# parasit.net
KiCad netlist of a schematic drawn in EAGLE
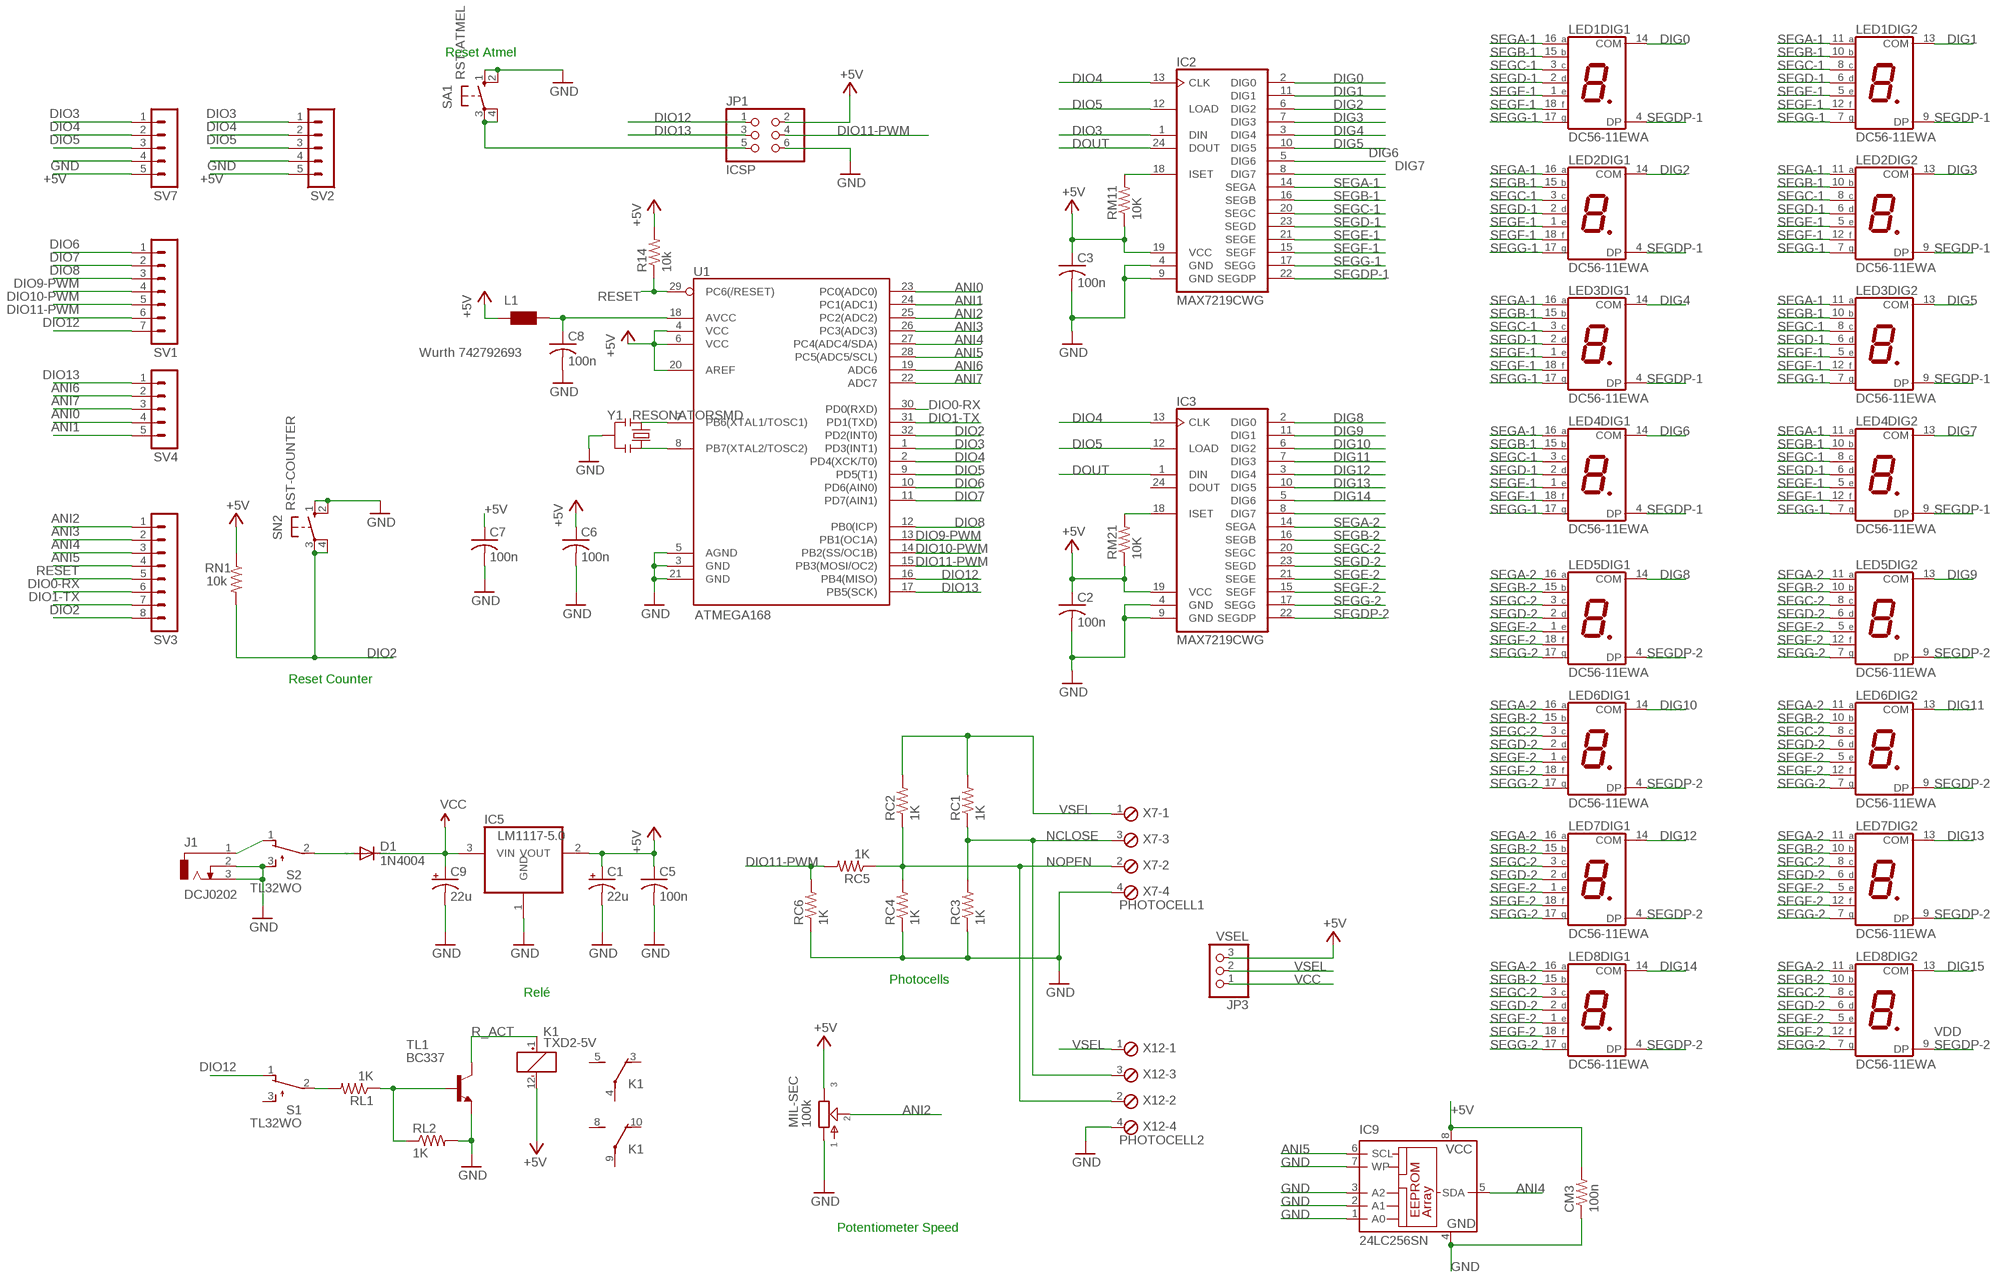
[diagram p0: schematic, sheet 1]

(export (version "E")
  (design (tool "Eeschema 10.0.6"))
  (components
    (comp (ref "C1")
      (value "22u")
      (footprint "eagle-import:PANASONIC_C")
      (libsource (lib "eagle-import") (part "CPOL-USC"))
    )
    (comp (ref "C2")
      (value "100n")
      (footprint "eagle-import:C0603")
      (libsource (lib "eagle-import") (part "C-USC0603"))
    )
    (comp (ref "C3")
      (value "100n")
      (footprint "eagle-import:C0603")
      (libsource (lib "eagle-import") (part "C-USC0603"))
    )
    (comp (ref "C5")
      (value "100n")
      (footprint "eagle-import:C0603")
      (libsource (lib "eagle-import") (part "C-USC0603"))
    )
    (comp (ref "C6")
      (value "100n")
      (footprint "eagle-import:C0603")
      (libsource (lib "eagle-import") (part "C-USC0603"))
    )
    (comp (ref "C7")
      (value "100n")
      (footprint "eagle-import:C0603")
      (libsource (lib "eagle-import") (part "C-USC0603"))
    )
    (comp (ref "C8")
      (value "100n")
      (footprint "eagle-import:C0603")
      (libsource (lib "eagle-import") (part "C-USC0603"))
    )
    (comp (ref "C9")
      (value "22u")
      (footprint "eagle-import:PANASONIC_C")
      (libsource (lib "eagle-import") (part "CPOL-USC"))
    )
    (comp (ref "CM3")
      (value "100n")
      (footprint "eagle-import:R0603")
      (libsource (lib "eagle-import") (part "resistor_R-US_R0603"))
    )
    (comp (ref "D1")
      (value "1N4004")
      (footprint "eagle-import:DO41-10")
      (libsource (lib "eagle-import") (part "1N4004"))
    )
    (comp (ref "IC2")
      (value "MAX7219CWG")
      (footprint "eagle-import:SO24W")
      (libsource (lib "eagle-import") (part "MAX7219WGC"))
    )
    (comp (ref "IC3")
      (value "MAX7219CWG")
      (footprint "eagle-import:SO24W")
      (libsource (lib "eagle-import") (part "MAX7219WGC"))
    )
    (comp (ref "IC5")
      (value "LM1117-5.0")
      (footprint "eagle-import:SOT223")
      (libsource (lib "eagle-import") (part "REG1117"))
    )
    (comp (ref "IC9")
      (value "24LC256SN")
      (footprint "eagle-import:SO-08")
      (fields (field (name "MF") "MICROCHIP") (field (name "MPN") "24LC256-I/SN"))
      (libsource (lib "eagle-import") (part "24SNLC256"))
    )
    (comp (ref "J1")
      (value "DCJ0202")
      (footprint "eagle-import:DCJ0202")
      (libsource (lib "eagle-import") (part "DCJ0202"))
    )
    (comp (ref "JP1")
      (value "ICSP")
      (footprint "eagle-import:2X03")
      (libsource (lib "eagle-import") (part "PINHD-2X3"))
    )
    (comp (ref "JP3")
      (value "VSEL")
      (footprint "eagle-import:1X03")
      (libsource (lib "eagle-import") (part "PINHD-1X3"))
    )
    (comp (ref "K1")
      (value "TXD2-5V")
      (footprint "eagle-import:TXD2")
      (libsource (lib "eagle-import") (part "TX?-D25V"))
    )
    (comp (ref "L1")
      (value "WE-CBF_0603")
      (footprint "eagle-import:0603")
      (libsource (lib "eagle-import") (part "WE-CBF_0603"))
    )
    (comp (ref "LED1")
      (value "DC56-11EWA")
      (footprint "eagle-import:DA56")
      (libsource (lib "eagle-import") (part "DC56-11EWA"))
    )
    (comp (ref "LED2")
      (value "DC56-11EWA")
      (footprint "eagle-import:DA56")
      (libsource (lib "eagle-import") (part "DC56-11EWA"))
    )
    (comp (ref "LED3")
      (value "DC56-11EWA")
      (footprint "eagle-import:DA56")
      (libsource (lib "eagle-import") (part "DC56-11EWA"))
    )
    (comp (ref "LED4")
      (value "DC56-11EWA")
      (footprint "eagle-import:DA56")
      (libsource (lib "eagle-import") (part "DC56-11EWA"))
    )
    (comp (ref "LED5")
      (value "DC56-11EWA")
      (footprint "eagle-import:DA56")
      (libsource (lib "eagle-import") (part "DC56-11EWA"))
    )
    (comp (ref "LED6")
      (value "DC56-11EWA")
      (footprint "eagle-import:DA56")
      (libsource (lib "eagle-import") (part "DC56-11EWA"))
    )
    (comp (ref "LED7")
      (value "DC56-11EWA")
      (footprint "eagle-import:DA56")
      (libsource (lib "eagle-import") (part "DC56-11EWA"))
    )
    (comp (ref "LED8")
      (value "DC56-11EWA")
      (footprint "eagle-import:DA56")
      (libsource (lib "eagle-import") (part "DC56-11EWA"))
    )
    (comp (ref "MIL-SEC")
      (value "100k")
      (footprint "eagle-import:16MM-PCB-BRACKETS@1")
      (libsource (lib "eagle-import") (part "16MM-PCB-BRACKETS"))
    )
    (comp (ref "R14")
      (value "10k")
      (footprint "eagle-import:R0603")
      (libsource (lib "eagle-import") (part "R-US_R0603"))
    )
    (comp (ref "RC1")
      (value "1K")
      (footprint "eagle-import:R0603")
      (libsource (lib "eagle-import") (part "R-US_R0603"))
    )
    (comp (ref "RC2")
      (value "1K")
      (footprint "eagle-import:R0603")
      (libsource (lib "eagle-import") (part "R-US_R0603"))
    )
    (comp (ref "RC3")
      (value "1K")
      (footprint "eagle-import:R0603")
      (libsource (lib "eagle-import") (part "R-US_R0603"))
    )
    (comp (ref "RC4")
      (value "1K")
      (footprint "eagle-import:R0603")
      (libsource (lib "eagle-import") (part "R-US_R0603"))
    )
    (comp (ref "RC5")
      (value "1K")
      (footprint "eagle-import:R0603")
      (libsource (lib "eagle-import") (part "R-US_R0603"))
    )
    (comp (ref "RC6")
      (value "1K")
      (footprint "eagle-import:R0603")
      (libsource (lib "eagle-import") (part "resistor_R-US_R0603"))
    )
    (comp (ref "RL1")
      (value "1K")
      (footprint "eagle-import:R0603")
      (libsource (lib "eagle-import") (part "resistor_R-US_R0603"))
    )
    (comp (ref "RL2")
      (value "1K")
      (footprint "eagle-import:R0603")
      (libsource (lib "eagle-import") (part "resistor_R-US_R0603"))
    )
    (comp (ref "RM11")
      (value "10K")
      (footprint "eagle-import:R0603")
      (libsource (lib "eagle-import") (part "R-US_R0603"))
    )
    (comp (ref "RM21")
      (value "10K")
      (footprint "eagle-import:R0603")
      (libsource (lib "eagle-import") (part "R-US_R0603"))
    )
    (comp (ref "RN1")
      (value "10k")
      (footprint "eagle-import:R0603")
      (libsource (lib "eagle-import") (part "R-US_R0603"))
    )
    (comp (ref "S1")
      (value "TL32WO")
      (footprint "eagle-import:TL3XWO")
      (libsource (lib "eagle-import") (part "TL32WO"))
    )
    (comp (ref "S2")
      (value "TL32WO")
      (footprint "eagle-import:TL3XWO")
      (libsource (lib "eagle-import") (part "TL32WO"))
    )
    (comp (ref "SA1")
      (value "RST-ATMEL")
      (footprint "eagle-import:B3F-10XX")
      (fields (field (name "MPN") "B3F-1000"))
      (libsource (lib "eagle-import") (part "10-XX"))
    )
    (comp (ref "SN2")
      (value "RST-COUNTER")
      (footprint "eagle-import:B3F-10XX")
      (fields (field (name "MPN") "B3F-1000"))
      (libsource (lib "eagle-import") (part "10-XX"))
    )
    (comp (ref "SV1")
      (value "MA07-1")
      (footprint "eagle-import:MA07-1")
      (libsource (lib "eagle-import") (part "MA07-1"))
    )
    (comp (ref "SV2")
      (value "MA05-1")
      (footprint "eagle-import:MA05-1")
      (libsource (lib "eagle-import") (part "MA05-1"))
    )
    (comp (ref "SV3")
      (value "MA08-1")
      (footprint "eagle-import:MA08-1")
      (libsource (lib "eagle-import") (part "MA08-1"))
    )
    (comp (ref "SV4")
      (value "MA05-1")
      (footprint "eagle-import:MA05-1")
      (libsource (lib "eagle-import") (part "MA05-1"))
    )
    (comp (ref "SV7")
      (value "MA05-1")
      (footprint "eagle-import:MA05-1")
      (libsource (lib "eagle-import") (part "MA05-1"))
    )
    (comp (ref "TL1")
      (value "BC337")
      (footprint "eagle-import:TO92")
      (libsource (lib "eagle-import") (part "BC337"))
    )
    (comp (ref "U1")
      (value "ATMEGA168")
      (footprint "eagle-import:TQFP32-08")
      (libsource (lib "eagle-import") (part "ATMEGA168"))
    )
    (comp (ref "X7")
      (value "PHOTOCELL1")
      (footprint "eagle-import:4POL254")
      (libsource (lib "eagle-import") (part "MPT4"))
    )
    (comp (ref "X12")
      (value "PHOTOCELL2")
      (footprint "eagle-import:4POL254")
      (libsource (lib "eagle-import") (part "MPT4"))
    )
    (comp (ref "Y1")
      (value "RESONATORSMD")
      (footprint "eagle-import:RESONATOR-SMD")
      (libsource (lib "eagle-import") (part "RESONATORSMD"))
    )
  )
  (nets
    (net (code "1") (name "+5V") (class "Default")
      (node (ref "C1") (pin "+") (pinfunction "+_+") (pintype "passive"))
      (node (ref "C2") (pin "1") (pinfunction "1_1") (pintype "passive"))
      (node (ref "C3") (pin "1") (pinfunction "1_1") (pintype "passive"))
      (node (ref "C5") (pin "1") (pinfunction "1_1") (pintype "passive"))
      (node (ref "C6") (pin "1") (pinfunction "1_1") (pintype "passive"))
      (node (ref "C7") (pin "1") (pinfunction "1_1") (pintype "passive"))
      (node (ref "CM3") (pin "2") (pinfunction "2_2") (pintype "passive"))
      (node (ref "IC2") (pin "19") (pinfunction "VCC_19") (pintype "power_in"))
      (node (ref "IC3") (pin "19") (pinfunction "VCC_19") (pintype "power_in"))
      (node (ref "IC5") (pin "2") (pinfunction "VOUT_2") (pintype "output"))
      (node (ref "IC9") (pin "8") (pinfunction "VCC_8") (pintype "power_in"))
      (node (ref "JP1") (pin "2") (pinfunction "2_2") (pintype "passive"))
      (node (ref "JP3") (pin "3") (pinfunction "3_3") (pintype "passive"))
      (node (ref "K1") (pin "12") (pinfunction "-_12") (pintype "passive"))
      (node (ref "L1") (pin "1") (pinfunction "1_1") (pintype "passive"))
      (node (ref "MIL-SEC") (pin "3") (pinfunction "3_3") (pintype "passive"))
      (node (ref "R14") (pin "2") (pinfunction "2_2") (pintype "passive"))
      (node (ref "RM11") (pin "1") (pinfunction "1_1") (pintype "passive"))
      (node (ref "RM21") (pin "1") (pinfunction "1_1") (pintype "passive"))
      (node (ref "RN1") (pin "1") (pinfunction "1_1") (pintype "passive"))
      (node (ref "SV2") (pin "5") (pinfunction "5_5") (pintype "passive"))
      (node (ref "SV7") (pin "5") (pinfunction "5_5") (pintype "passive"))
      (node (ref "U1") (pin "20") (pinfunction "AREF_20") (pintype "bidirectional"))
      (node (ref "U1") (pin "4") (pinfunction "VCC_4") (pintype "bidirectional"))
      (node (ref "U1") (pin "6") (pinfunction "VCC_6") (pintype "bidirectional"))
    )
    (net (code "2") (name "/ANI0") (class "Default")
      (node (ref "SV4") (pin "4") (pinfunction "4_4") (pintype "passive"))
      (node (ref "U1") (pin "23") (pinfunction "PC0(ADC0)_23") (pintype "bidirectional"))
    )
    (net (code "3") (name "/ANI1") (class "Default")
      (node (ref "SV4") (pin "5") (pinfunction "5_5") (pintype "passive"))
      (node (ref "U1") (pin "24") (pinfunction "PC1(ADC1)_24") (pintype "bidirectional"))
    )
    (net (code "4") (name "/ANI2") (class "Default")
      (node (ref "MIL-SEC") (pin "2") (pinfunction "2_2") (pintype "passive"))
      (node (ref "SV3") (pin "1") (pinfunction "1_1") (pintype "passive"))
      (node (ref "U1") (pin "25") (pinfunction "PC2(ADC2)_25") (pintype "bidirectional"))
    )
    (net (code "5") (name "/ANI3") (class "Default")
      (node (ref "SV3") (pin "2") (pinfunction "2_2") (pintype "passive"))
      (node (ref "U1") (pin "26") (pinfunction "PC3(ADC3)_26") (pintype "bidirectional"))
    )
    (net (code "6") (name "/ANI4") (class "Default")
      (node (ref "IC9") (pin "5") (pinfunction "SDA_5") (pintype "bidirectional"))
      (node (ref "SV3") (pin "3") (pinfunction "3_3") (pintype "passive"))
      (node (ref "U1") (pin "27") (pinfunction "PC4(ADC4/SDA)_27") (pintype "bidirectional"))
    )
    (net (code "7") (name "/ANI5") (class "Default")
      (node (ref "IC9") (pin "6") (pinfunction "SCL_6") (pintype "input"))
      (node (ref "SV3") (pin "4") (pinfunction "4_4") (pintype "passive"))
      (node (ref "U1") (pin "28") (pinfunction "PC5(ADC5/SCL)_28") (pintype "bidirectional"))
    )
    (net (code "8") (name "/ANI6") (class "Default")
      (node (ref "SV4") (pin "2") (pinfunction "2_2") (pintype "passive"))
      (node (ref "U1") (pin "19") (pinfunction "ADC6_19") (pintype "bidirectional"))
    )
    (net (code "9") (name "/ANI7") (class "Default")
      (node (ref "SV4") (pin "3") (pinfunction "3_3") (pintype "passive"))
      (node (ref "U1") (pin "22") (pinfunction "ADC7_22") (pintype "bidirectional"))
    )
    (net (code "10") (name "/DIG0") (class "Default")
      (node (ref "IC2") (pin "2") (pinfunction "DIG0_2") (pintype "output"))
      (node (ref "LED1") (pin "14") (pinfunction "COM_14") (pintype "passive"))
    )
    (net (code "11") (name "/DIG1") (class "Default")
      (node (ref "IC2") (pin "11") (pinfunction "DIG1_11") (pintype "output"))
      (node (ref "LED1") (pin "13") (pinfunction "COM_13") (pintype "passive"))
    )
    (net (code "12") (name "/DIG2") (class "Default")
      (node (ref "IC2") (pin "6") (pinfunction "DIG2_6") (pintype "output"))
      (node (ref "LED2") (pin "14") (pinfunction "COM_14") (pintype "passive"))
    )
    (net (code "13") (name "/DIG3") (class "Default")
      (node (ref "IC2") (pin "7") (pinfunction "DIG3_7") (pintype "output"))
      (node (ref "LED2") (pin "13") (pinfunction "COM_13") (pintype "passive"))
    )
    (net (code "14") (name "/DIG4") (class "Default")
      (node (ref "IC2") (pin "3") (pinfunction "DIG4_3") (pintype "output"))
      (node (ref "LED3") (pin "14") (pinfunction "COM_14") (pintype "passive"))
    )
    (net (code "15") (name "/DIG5") (class "Default")
      (node (ref "IC2") (pin "10") (pinfunction "DIG5_10") (pintype "output"))
      (node (ref "LED3") (pin "13") (pinfunction "COM_13") (pintype "passive"))
    )
    (net (code "16") (name "/DIG6") (class "Default")
      (node (ref "IC2") (pin "5") (pinfunction "DIG6_5") (pintype "output"))
      (node (ref "LED4") (pin "14") (pinfunction "COM_14") (pintype "passive"))
    )
    (net (code "17") (name "/DIG7") (class "Default")
      (node (ref "IC2") (pin "8") (pinfunction "DIG7_8") (pintype "output"))
      (node (ref "LED4") (pin "13") (pinfunction "COM_13") (pintype "passive"))
    )
    (net (code "18") (name "/DIG8") (class "Default")
      (node (ref "IC3") (pin "2") (pinfunction "DIG0_2") (pintype "output"))
      (node (ref "LED5") (pin "14") (pinfunction "COM_14") (pintype "passive"))
    )
    (net (code "19") (name "/DIG9") (class "Default")
      (node (ref "IC3") (pin "11") (pinfunction "DIG1_11") (pintype "output"))
      (node (ref "LED5") (pin "13") (pinfunction "COM_13") (pintype "passive"))
    )
    (net (code "20") (name "/DIG10") (class "Default")
      (node (ref "IC3") (pin "6") (pinfunction "DIG2_6") (pintype "output"))
      (node (ref "LED6") (pin "14") (pinfunction "COM_14") (pintype "passive"))
    )
    (net (code "21") (name "/DIG11") (class "Default")
      (node (ref "IC3") (pin "7") (pinfunction "DIG3_7") (pintype "output"))
      (node (ref "LED6") (pin "13") (pinfunction "COM_13") (pintype "passive"))
    )
    (net (code "22") (name "/DIG12") (class "Default")
      (node (ref "IC3") (pin "3") (pinfunction "DIG4_3") (pintype "output"))
      (node (ref "LED7") (pin "14") (pinfunction "COM_14") (pintype "passive"))
    )
    (net (code "23") (name "/DIG13") (class "Default")
      (node (ref "IC3") (pin "10") (pinfunction "DIG5_10") (pintype "output"))
      (node (ref "LED7") (pin "13") (pinfunction "COM_13") (pintype "passive"))
    )
    (net (code "24") (name "/DIG14") (class "Default")
      (node (ref "IC3") (pin "5") (pinfunction "DIG6_5") (pintype "output"))
      (node (ref "LED8") (pin "14") (pinfunction "COM_14") (pintype "passive"))
    )
    (net (code "25") (name "/DIG15") (class "Default")
      (node (ref "IC3") (pin "8") (pinfunction "DIG7_8") (pintype "output"))
      (node (ref "LED8") (pin "13") (pinfunction "COM_13") (pintype "passive"))
    )
    (net (code "26") (name "/DIO0-RX") (class "Default")
      (node (ref "SV3") (pin "6") (pinfunction "6_6") (pintype "passive"))
      (node (ref "U1") (pin "30") (pinfunction "PD0(RXD)_30") (pintype "bidirectional"))
    )
    (net (code "27") (name "/DIO1-TX") (class "Default")
      (node (ref "SV3") (pin "7") (pinfunction "7_7") (pintype "passive"))
      (node (ref "U1") (pin "31") (pinfunction "PD1(TXD)_31") (pintype "bidirectional"))
    )
    (net (code "28") (name "/DIO2") (class "Default")
      (node (ref "RN1") (pin "2") (pinfunction "2_2") (pintype "passive"))
      (node (ref "SN2") (pin "3") (pinfunction "P_3") (pintype "passive"))
      (node (ref "SN2") (pin "4") (pinfunction "P1_4") (pintype "passive"))
      (node (ref "SV3") (pin "8") (pinfunction "8_8") (pintype "passive"))
      (node (ref "U1") (pin "32") (pinfunction "PD2(INT0)_32") (pintype "bidirectional"))
    )
    (net (code "29") (name "/DIO3") (class "Default")
      (node (ref "IC2") (pin "1") (pinfunction "DIN_1") (pintype "input"))
      (node (ref "SV2") (pin "1") (pinfunction "1_1") (pintype "passive"))
      (node (ref "SV7") (pin "1") (pinfunction "1_1") (pintype "passive"))
      (node (ref "U1") (pin "1") (pinfunction "PD3(INT1)_1") (pintype "bidirectional"))
    )
    (net (code "30") (name "/DIO4") (class "Default")
      (node (ref "IC2") (pin "13") (pinfunction "CLK_13") (pintype "input"))
      (node (ref "IC3") (pin "13") (pinfunction "CLK_13") (pintype "input"))
      (node (ref "SV2") (pin "2") (pinfunction "2_2") (pintype "passive"))
      (node (ref "SV7") (pin "2") (pinfunction "2_2") (pintype "passive"))
      (node (ref "U1") (pin "2") (pinfunction "PD4(XCK/T0)_2") (pintype "bidirectional"))
    )
    (net (code "31") (name "/DIO5") (class "Default")
      (node (ref "IC2") (pin "12") (pinfunction "LOAD_12") (pintype "input"))
      (node (ref "IC3") (pin "12") (pinfunction "LOAD_12") (pintype "input"))
      (node (ref "SV2") (pin "3") (pinfunction "3_3") (pintype "passive"))
      (node (ref "SV7") (pin "3") (pinfunction "3_3") (pintype "passive"))
      (node (ref "U1") (pin "9") (pinfunction "PD5(T1)_9") (pintype "bidirectional"))
    )
    (net (code "32") (name "/DIO6") (class "Default")
      (node (ref "SV1") (pin "1") (pinfunction "1_1") (pintype "passive"))
      (node (ref "U1") (pin "10") (pinfunction "PD6(AIN0)_10") (pintype "bidirectional"))
    )
    (net (code "33") (name "/DIO7") (class "Default")
      (node (ref "SV1") (pin "2") (pinfunction "2_2") (pintype "passive"))
      (node (ref "U1") (pin "11") (pinfunction "PD7(AIN1)_11") (pintype "bidirectional"))
    )
    (net (code "34") (name "/DIO8") (class "Default")
      (node (ref "SV1") (pin "3") (pinfunction "3_3") (pintype "passive"))
      (node (ref "U1") (pin "12") (pinfunction "PB0(ICP)_12") (pintype "bidirectional"))
    )
    (net (code "35") (name "/DIO9-PWM") (class "Default")
      (node (ref "SV1") (pin "4") (pinfunction "4_4") (pintype "passive"))
      (node (ref "U1") (pin "13") (pinfunction "PB1(OC1A)_13") (pintype "bidirectional"))
    )
    (net (code "36") (name "/DIO10-PWM") (class "Default")
      (node (ref "SV1") (pin "5") (pinfunction "5_5") (pintype "passive"))
      (node (ref "U1") (pin "14") (pinfunction "PB2(SS/OC1B)_14") (pintype "bidirectional"))
    )
    (net (code "37") (name "/DIO11-PWM") (class "Default")
      (node (ref "JP1") (pin "4") (pinfunction "4_4") (pintype "passive"))
      (node (ref "RC5") (pin "2") (pinfunction "2_2") (pintype "passive"))
      (node (ref "RC6") (pin "2") (pinfunction "2_2") (pintype "passive"))
      (node (ref "SV1") (pin "6") (pinfunction "6_6") (pintype "passive"))
      (node (ref "U1") (pin "15") (pinfunction "PB3(MOSI/OC2)_15") (pintype "bidirectional"))
    )
    (net (code "38") (name "/DIO12") (class "Default")
      (node (ref "JP1") (pin "1") (pinfunction "1_1") (pintype "passive"))
      (node (ref "S1") (pin "1") (pinfunction "O_1") (pintype "passive"))
      (node (ref "SV1") (pin "7") (pinfunction "7_7") (pintype "passive"))
      (node (ref "U1") (pin "16") (pinfunction "PB4(MISO)_16") (pintype "bidirectional"))
    )
    (net (code "39") (name "/DIO13") (class "Default")
      (node (ref "JP1") (pin "3") (pinfunction "3_3") (pintype "passive"))
      (node (ref "SV4") (pin "1") (pinfunction "1_1") (pintype "passive"))
      (node (ref "U1") (pin "17") (pinfunction "PB5(SCK)_17") (pintype "bidirectional"))
    )
    (net (code "40") (name "/DOUT") (class "Default")
      (node (ref "IC2") (pin "24") (pinfunction "DOUT_24") (pintype "output"))
      (node (ref "IC3") (pin "1") (pinfunction "DIN_1") (pintype "input"))
    )
    (net (code "41") (name "/NCLOSE") (class "Default")
      (node (ref "RC1") (pin "1") (pinfunction "1_1") (pintype "passive"))
      (node (ref "RC3") (pin "2") (pinfunction "2_2") (pintype "passive"))
      (node (ref "X12") (pin "3") (pinfunction "1_3") (pintype "passive"))
      (node (ref "X7") (pin "3") (pinfunction "1_3") (pintype "passive"))
    )
    (net (code "42") (name "/NOPEN") (class "Default")
      (node (ref "RC2") (pin "1") (pinfunction "1_1") (pintype "passive"))
      (node (ref "RC4") (pin "2") (pinfunction "2_2") (pintype "passive"))
      (node (ref "RC5") (pin "1") (pinfunction "1_1") (pintype "passive"))
      (node (ref "X12") (pin "2") (pinfunction "1_2") (pintype "passive"))
      (node (ref "X7") (pin "2") (pinfunction "1_2") (pintype "passive"))
    )
    (net (code "43") (name "/RESET") (class "Default")
      (node (ref "JP1") (pin "5") (pinfunction "5_5") (pintype "passive"))
      (node (ref "R14") (pin "1") (pinfunction "1_1") (pintype "passive"))
      (node (ref "SA1") (pin "3") (pinfunction "P_3") (pintype "passive"))
      (node (ref "SA1") (pin "4") (pinfunction "P1_4") (pintype "passive"))
      (node (ref "SV3") (pin "5") (pinfunction "5_5") (pintype "passive"))
      (node (ref "U1") (pin "29") (pinfunction "PC6(/RESET)_29") (pintype "bidirectional"))
    )
    (net (code "44") (name "/R_ACT") (class "Default")
      (node (ref "K1") (pin "1") (pinfunction "+_1") (pintype "passive"))
      (node (ref "TL1") (pin "3") (pinfunction "C_3") (pintype "passive"))
    )
    (net (code "45") (name "/SEGA-1") (class "Default")
      (node (ref "IC2") (pin "14") (pinfunction "SEGA_14") (pintype "output"))
      (node (ref "LED1") (pin "11") (pinfunction "A_11") (pintype "passive"))
      (node (ref "LED1") (pin "16") (pinfunction "A_16") (pintype "passive"))
      (node (ref "LED2") (pin "11") (pinfunction "A_11") (pintype "passive"))
      (node (ref "LED2") (pin "16") (pinfunction "A_16") (pintype "passive"))
      (node (ref "LED3") (pin "11") (pinfunction "A_11") (pintype "passive"))
      (node (ref "LED3") (pin "16") (pinfunction "A_16") (pintype "passive"))
      (node (ref "LED4") (pin "11") (pinfunction "A_11") (pintype "passive"))
      (node (ref "LED4") (pin "16") (pinfunction "A_16") (pintype "passive"))
    )
    (net (code "46") (name "/SEGA-2") (class "Default")
      (node (ref "IC3") (pin "14") (pinfunction "SEGA_14") (pintype "output"))
      (node (ref "LED5") (pin "11") (pinfunction "A_11") (pintype "passive"))
      (node (ref "LED5") (pin "16") (pinfunction "A_16") (pintype "passive"))
      (node (ref "LED6") (pin "11") (pinfunction "A_11") (pintype "passive"))
      (node (ref "LED6") (pin "16") (pinfunction "A_16") (pintype "passive"))
      (node (ref "LED7") (pin "11") (pinfunction "A_11") (pintype "passive"))
      (node (ref "LED7") (pin "16") (pinfunction "A_16") (pintype "passive"))
      (node (ref "LED8") (pin "11") (pinfunction "A_11") (pintype "passive"))
      (node (ref "LED8") (pin "16") (pinfunction "A_16") (pintype "passive"))
    )
    (net (code "47") (name "/SEGB-1") (class "Default")
      (node (ref "IC2") (pin "16") (pinfunction "SEGB_16") (pintype "output"))
      (node (ref "LED1") (pin "10") (pinfunction "B_10") (pintype "passive"))
      (node (ref "LED1") (pin "15") (pinfunction "B_15") (pintype "passive"))
      (node (ref "LED2") (pin "10") (pinfunction "B_10") (pintype "passive"))
      (node (ref "LED2") (pin "15") (pinfunction "B_15") (pintype "passive"))
      (node (ref "LED3") (pin "10") (pinfunction "B_10") (pintype "passive"))
      (node (ref "LED3") (pin "15") (pinfunction "B_15") (pintype "passive"))
      (node (ref "LED4") (pin "10") (pinfunction "B_10") (pintype "passive"))
      (node (ref "LED4") (pin "15") (pinfunction "B_15") (pintype "passive"))
    )
    (net (code "48") (name "/SEGB-2") (class "Default")
      (node (ref "IC3") (pin "16") (pinfunction "SEGB_16") (pintype "output"))
      (node (ref "LED5") (pin "10") (pinfunction "B_10") (pintype "passive"))
      (node (ref "LED5") (pin "15") (pinfunction "B_15") (pintype "passive"))
      (node (ref "LED6") (pin "10") (pinfunction "B_10") (pintype "passive"))
      (node (ref "LED6") (pin "15") (pinfunction "B_15") (pintype "passive"))
      (node (ref "LED7") (pin "10") (pinfunction "B_10") (pintype "passive"))
      (node (ref "LED7") (pin "15") (pinfunction "B_15") (pintype "passive"))
      (node (ref "LED8") (pin "10") (pinfunction "B_10") (pintype "passive"))
      (node (ref "LED8") (pin "15") (pinfunction "B_15") (pintype "passive"))
    )
    (net (code "49") (name "/SEGC-1") (class "Default")
      (node (ref "IC2") (pin "20") (pinfunction "SEGC_20") (pintype "output"))
      (node (ref "LED1") (pin "3") (pinfunction "C_3") (pintype "passive"))
      (node (ref "LED1") (pin "8") (pinfunction "C_8") (pintype "passive"))
      (node (ref "LED2") (pin "3") (pinfunction "C_3") (pintype "passive"))
      (node (ref "LED2") (pin "8") (pinfunction "C_8") (pintype "passive"))
      (node (ref "LED3") (pin "3") (pinfunction "C_3") (pintype "passive"))
      (node (ref "LED3") (pin "8") (pinfunction "C_8") (pintype "passive"))
      (node (ref "LED4") (pin "3") (pinfunction "C_3") (pintype "passive"))
      (node (ref "LED4") (pin "8") (pinfunction "C_8") (pintype "passive"))
    )
    (net (code "50") (name "/SEGC-2") (class "Default")
      (node (ref "IC3") (pin "20") (pinfunction "SEGC_20") (pintype "output"))
      (node (ref "LED5") (pin "3") (pinfunction "C_3") (pintype "passive"))
      (node (ref "LED5") (pin "8") (pinfunction "C_8") (pintype "passive"))
      (node (ref "LED6") (pin "3") (pinfunction "C_3") (pintype "passive"))
      (node (ref "LED6") (pin "8") (pinfunction "C_8") (pintype "passive"))
      (node (ref "LED7") (pin "3") (pinfunction "C_3") (pintype "passive"))
      (node (ref "LED7") (pin "8") (pinfunction "C_8") (pintype "passive"))
      (node (ref "LED8") (pin "3") (pinfunction "C_3") (pintype "passive"))
      (node (ref "LED8") (pin "8") (pinfunction "C_8") (pintype "passive"))
    )
    (net (code "51") (name "/SEGD-1") (class "Default")
      (node (ref "IC2") (pin "23") (pinfunction "SEGD_23") (pintype "output"))
      (node (ref "LED1") (pin "2") (pinfunction "D_2") (pintype "passive"))
      (node (ref "LED1") (pin "6") (pinfunction "D_6") (pintype "passive"))
      (node (ref "LED2") (pin "2") (pinfunction "D_2") (pintype "passive"))
      (node (ref "LED2") (pin "6") (pinfunction "D_6") (pintype "passive"))
      (node (ref "LED3") (pin "2") (pinfunction "D_2") (pintype "passive"))
      (node (ref "LED3") (pin "6") (pinfunction "D_6") (pintype "passive"))
      (node (ref "LED4") (pin "2") (pinfunction "D_2") (pintype "passive"))
      (node (ref "LED4") (pin "6") (pinfunction "D_6") (pintype "passive"))
    )
    (net (code "52") (name "/SEGD-2") (class "Default")
      (node (ref "IC3") (pin "23") (pinfunction "SEGD_23") (pintype "output"))
      (node (ref "LED5") (pin "2") (pinfunction "D_2") (pintype "passive"))
      (node (ref "LED5") (pin "6") (pinfunction "D_6") (pintype "passive"))
      (node (ref "LED6") (pin "2") (pinfunction "D_2") (pintype "passive"))
      (node (ref "LED6") (pin "6") (pinfunction "D_6") (pintype "passive"))
      (node (ref "LED7") (pin "2") (pinfunction "D_2") (pintype "passive"))
      (node (ref "LED7") (pin "6") (pinfunction "D_6") (pintype "passive"))
      (node (ref "LED8") (pin "2") (pinfunction "D_2") (pintype "passive"))
      (node (ref "LED8") (pin "6") (pinfunction "D_6") (pintype "passive"))
    )
    (net (code "53") (name "/SEGDP-1") (class "Default")
      (node (ref "IC2") (pin "22") (pinfunction "SEGDP_22") (pintype "output"))
      (node (ref "LED1") (pin "4") (pinfunction "DP_4") (pintype "passive"))
      (node (ref "LED1") (pin "9") (pinfunction "DP_9") (pintype "passive"))
      (node (ref "LED2") (pin "4") (pinfunction "DP_4") (pintype "passive"))
      (node (ref "LED2") (pin "9") (pinfunction "DP_9") (pintype "passive"))
      (node (ref "LED3") (pin "4") (pinfunction "DP_4") (pintype "passive"))
      (node (ref "LED3") (pin "9") (pinfunction "DP_9") (pintype "passive"))
      (node (ref "LED4") (pin "4") (pinfunction "DP_4") (pintype "passive"))
      (node (ref "LED4") (pin "9") (pinfunction "DP_9") (pintype "passive"))
    )
    (net (code "54") (name "/SEGDP-2") (class "Default")
      (node (ref "IC3") (pin "22") (pinfunction "SEGDP_22") (pintype "output"))
      (node (ref "LED5") (pin "4") (pinfunction "DP_4") (pintype "passive"))
      (node (ref "LED5") (pin "9") (pinfunction "DP_9") (pintype "passive"))
      (node (ref "LED6") (pin "4") (pinfunction "DP_4") (pintype "passive"))
      (node (ref "LED6") (pin "9") (pinfunction "DP_9") (pintype "passive"))
      (node (ref "LED7") (pin "4") (pinfunction "DP_4") (pintype "passive"))
      (node (ref "LED7") (pin "9") (pinfunction "DP_9") (pintype "passive"))
      (node (ref "LED8") (pin "4") (pinfunction "DP_4") (pintype "passive"))
      (node (ref "LED8") (pin "9") (pinfunction "DP_9") (pintype "passive"))
    )
    (net (code "55") (name "/SEGE-1") (class "Default")
      (node (ref "IC2") (pin "21") (pinfunction "SEGE_21") (pintype "output"))
      (node (ref "LED1") (pin "1") (pinfunction "E_1") (pintype "passive"))
      (node (ref "LED1") (pin "5") (pinfunction "E_5") (pintype "passive"))
      (node (ref "LED2") (pin "1") (pinfunction "E_1") (pintype "passive"))
      (node (ref "LED2") (pin "5") (pinfunction "E_5") (pintype "passive"))
      (node (ref "LED3") (pin "1") (pinfunction "E_1") (pintype "passive"))
      (node (ref "LED3") (pin "5") (pinfunction "E_5") (pintype "passive"))
      (node (ref "LED4") (pin "1") (pinfunction "E_1") (pintype "passive"))
      (node (ref "LED4") (pin "5") (pinfunction "E_5") (pintype "passive"))
    )
    (net (code "56") (name "/SEGE-2") (class "Default")
      (node (ref "IC3") (pin "21") (pinfunction "SEGE_21") (pintype "output"))
      (node (ref "LED5") (pin "1") (pinfunction "E_1") (pintype "passive"))
      (node (ref "LED5") (pin "5") (pinfunction "E_5") (pintype "passive"))
      (node (ref "LED6") (pin "1") (pinfunction "E_1") (pintype "passive"))
      (node (ref "LED6") (pin "5") (pinfunction "E_5") (pintype "passive"))
      (node (ref "LED7") (pin "1") (pinfunction "E_1") (pintype "passive"))
      (node (ref "LED7") (pin "5") (pinfunction "E_5") (pintype "passive"))
      (node (ref "LED8") (pin "1") (pinfunction "E_1") (pintype "passive"))
      (node (ref "LED8") (pin "5") (pinfunction "E_5") (pintype "passive"))
    )
    (net (code "57") (name "/SEGF-1") (class "Default")
      (node (ref "IC2") (pin "15") (pinfunction "SEGF_15") (pintype "output"))
      (node (ref "LED1") (pin "12") (pinfunction "F_12") (pintype "passive"))
      (node (ref "LED1") (pin "18") (pinfunction "F_18") (pintype "passive"))
      (node (ref "LED2") (pin "12") (pinfunction "F_12") (pintype "passive"))
      (node (ref "LED2") (pin "18") (pinfunction "F_18") (pintype "passive"))
      (node (ref "LED3") (pin "12") (pinfunction "F_12") (pintype "passive"))
      (node (ref "LED3") (pin "18") (pinfunction "F_18") (pintype "passive"))
      (node (ref "LED4") (pin "12") (pinfunction "F_12") (pintype "passive"))
      (node (ref "LED4") (pin "18") (pinfunction "F_18") (pintype "passive"))
    )
    (net (code "58") (name "/SEGF-2") (class "Default")
      (node (ref "IC3") (pin "15") (pinfunction "SEGF_15") (pintype "output"))
      (node (ref "LED5") (pin "12") (pinfunction "F_12") (pintype "passive"))
      (node (ref "LED5") (pin "18") (pinfunction "F_18") (pintype "passive"))
      (node (ref "LED6") (pin "12") (pinfunction "F_12") (pintype "passive"))
      (node (ref "LED6") (pin "18") (pinfunction "F_18") (pintype "passive"))
      (node (ref "LED7") (pin "12") (pinfunction "F_12") (pintype "passive"))
      (node (ref "LED7") (pin "18") (pinfunction "F_18") (pintype "passive"))
      (node (ref "LED8") (pin "12") (pinfunction "F_12") (pintype "passive"))
      (node (ref "LED8") (pin "18") (pinfunction "F_18") (pintype "passive"))
    )
    (net (code "59") (name "/SEGG-1") (class "Default")
      (node (ref "IC2") (pin "17") (pinfunction "SEGG_17") (pintype "output"))
      (node (ref "LED1") (pin "17") (pinfunction "G_17") (pintype "passive"))
      (node (ref "LED1") (pin "7") (pinfunction "G_7") (pintype "passive"))
      (node (ref "LED2") (pin "17") (pinfunction "G_17") (pintype "passive"))
      (node (ref "LED2") (pin "7") (pinfunction "G_7") (pintype "passive"))
      (node (ref "LED3") (pin "17") (pinfunction "G_17") (pintype "passive"))
      (node (ref "LED3") (pin "7") (pinfunction "G_7") (pintype "passive"))
      (node (ref "LED4") (pin "17") (pinfunction "G_17") (pintype "passive"))
      (node (ref "LED4") (pin "7") (pinfunction "G_7") (pintype "passive"))
    )
    (net (code "60") (name "/SEGG-2") (class "Default")
      (node (ref "IC3") (pin "17") (pinfunction "SEGG_17") (pintype "output"))
      (node (ref "LED5") (pin "17") (pinfunction "G_17") (pintype "passive"))
      (node (ref "LED5") (pin "7") (pinfunction "G_7") (pintype "passive"))
      (node (ref "LED6") (pin "17") (pinfunction "G_17") (pintype "passive"))
      (node (ref "LED6") (pin "7") (pinfunction "G_7") (pintype "passive"))
      (node (ref "LED7") (pin "17") (pinfunction "G_17") (pintype "passive"))
      (node (ref "LED7") (pin "7") (pinfunction "G_7") (pintype "passive"))
      (node (ref "LED8") (pin "17") (pinfunction "G_17") (pintype "passive"))
      (node (ref "LED8") (pin "7") (pinfunction "G_7") (pintype "passive"))
    )
    (net (code "62") (name "/VSEL") (class "Default")
      (node (ref "JP3") (pin "2") (pinfunction "2_2") (pintype "passive"))
      (node (ref "RC1") (pin "2") (pinfunction "2_2") (pintype "passive"))
      (node (ref "RC2") (pin "2") (pinfunction "2_2") (pintype "passive"))
      (node (ref "X12") (pin "1") (pinfunction "1_1") (pintype "passive"))
      (node (ref "X7") (pin "1") (pinfunction "1_1") (pintype "passive"))
    )
    (net (code "63") (name "GND") (class "Default")
      (node (ref "C1") (pin "-") (pinfunction "-_-") (pintype "passive"))
      (node (ref "C2") (pin "2") (pinfunction "2_2") (pintype "passive"))
      (node (ref "C3") (pin "2") (pinfunction "2_2") (pintype "passive"))
      (node (ref "C5") (pin "2") (pinfunction "2_2") (pintype "passive"))
      (node (ref "C6") (pin "2") (pinfunction "2_2") (pintype "passive"))
      (node (ref "C7") (pin "2") (pinfunction "2_2") (pintype "passive"))
      (node (ref "C8") (pin "2") (pinfunction "2_2") (pintype "passive"))
      (node (ref "C9") (pin "-") (pinfunction "-_-") (pintype "passive"))
      (node (ref "CM3") (pin "1") (pinfunction "1_1") (pintype "passive"))
      (node (ref "IC2") (pin "4") (pinfunction "GND_4") (pintype "power_in"))
      (node (ref "IC2") (pin "9") (pinfunction "GND_9") (pintype "power_in"))
      (node (ref "IC3") (pin "4") (pinfunction "GND_4") (pintype "power_in"))
      (node (ref "IC3") (pin "9") (pinfunction "GND_9") (pintype "power_in"))
      (node (ref "IC5") (pin "1") (pinfunction "GND_1") (pintype "power_in"))
      (node (ref "IC9") (pin "1") (pinfunction "A0_1") (pintype "input"))
      (node (ref "IC9") (pin "2") (pinfunction "A1_2") (pintype "input"))
      (node (ref "IC9") (pin "3") (pinfunction "A2_3") (pintype "input"))
      (node (ref "IC9") (pin "4") (pinfunction "GND_4") (pintype "power_in"))
      (node (ref "IC9") (pin "7") (pinfunction "WP_7") (pintype "input"))
      (node (ref "J1") (pin "2") (pinfunction "2_2") (pintype "passive"))
      (node (ref "J1") (pin "3") (pinfunction "3_3") (pintype "passive"))
      (node (ref "JP1") (pin "6") (pinfunction "6_6") (pintype "passive"))
      (node (ref "MIL-SEC") (pin "1") (pinfunction "1_1") (pintype "passive"))
      (node (ref "RC3") (pin "1") (pinfunction "1_1") (pintype "passive"))
      (node (ref "RC4") (pin "1") (pinfunction "1_1") (pintype "passive"))
      (node (ref "RC6") (pin "1") (pinfunction "1_1") (pintype "passive"))
      (node (ref "RL2") (pin "2") (pinfunction "2_2") (pintype "passive"))
      (node (ref "S2") (pin "3") (pinfunction "S_3") (pintype "passive"))
      (node (ref "SA1") (pin "1") (pinfunction "S_1") (pintype "passive"))
      (node (ref "SA1") (pin "2") (pinfunction "S1_2") (pintype "passive"))
      (node (ref "SN2") (pin "1") (pinfunction "S_1") (pintype "passive"))
      (node (ref "SN2") (pin "2") (pinfunction "S1_2") (pintype "passive"))
      (node (ref "SV2") (pin "4") (pinfunction "4_4") (pintype "passive"))
      (node (ref "SV7") (pin "4") (pinfunction "4_4") (pintype "passive"))
      (node (ref "TL1") (pin "1") (pinfunction "E_1") (pintype "passive"))
      (node (ref "U1") (pin "21") (pinfunction "GND_21") (pintype "bidirectional"))
      (node (ref "U1") (pin "3") (pinfunction "GND_3") (pintype "bidirectional"))
      (node (ref "U1") (pin "5") (pinfunction "AGND_5") (pintype "bidirectional"))
      (node (ref "X12") (pin "4") (pinfunction "1_4") (pintype "passive"))
      (node (ref "X7") (pin "4") (pinfunction "1_4") (pintype "passive"))
      (node (ref "Y1") (pin "2") (pinfunction "2_2") (pintype "passive"))
    )
    (net (code "64") (name "Net-(IC2-ISET)") (class "Default")
      (node (ref "IC2") (pin "18") (pinfunction "ISET_18") (pintype "input"))
      (node (ref "RM11") (pin "2") (pinfunction "2_2") (pintype "passive"))
    )
    (net (code "65") (name "Net-(IC3-ISET)") (class "Default")
      (node (ref "IC3") (pin "18") (pinfunction "ISET_18") (pintype "input"))
      (node (ref "RM21") (pin "2") (pinfunction "2_2") (pintype "passive"))
    )
    (net (code "66") (name "Net-(S1-P)") (class "Default")
      (node (ref "RL1") (pin "2") (pinfunction "2_2") (pintype "passive"))
      (node (ref "S1") (pin "2") (pinfunction "P_2") (pintype "passive"))
    )
    (net (code "67") (name "Net-(S2-O)") (class "Default")
      (node (ref "J1") (pin "1") (pinfunction "1_1") (pintype "passive"))
      (node (ref "S2") (pin "1") (pinfunction "O_1") (pintype "passive"))
    )
    (net (code "68") (name "Net-(S2-P)") (class "Default")
      (node (ref "D1") (pin "A") (pinfunction "A_A") (pintype "passive"))
      (node (ref "S2") (pin "2") (pinfunction "P_2") (pintype "passive"))
    )
    (net (code "69") (name "Net-(TL1-B)") (class "Default")
      (node (ref "RL1") (pin "1") (pinfunction "1_1") (pintype "passive"))
      (node (ref "RL2") (pin "1") (pinfunction "1_1") (pintype "passive"))
      (node (ref "TL1") (pin "2") (pinfunction "B_2") (pintype "passive"))
    )
    (net (code "70") (name "Net-(U1-AVCC)") (class "Default")
      (node (ref "C8") (pin "1") (pinfunction "1_1") (pintype "passive"))
      (node (ref "L1") (pin "2") (pinfunction "2_2") (pintype "passive"))
      (node (ref "U1") (pin "18") (pinfunction "AVCC_18") (pintype "bidirectional"))
    )
    (net (code "71") (name "Net-(U1-PB6(XTAL1{slash}TOSC1))") (class "Default")
      (node (ref "U1") (pin "7") (pinfunction "PB6(XTAL1/TOSC1)_7") (pintype "bidirectional"))
      (node (ref "Y1") (pin "1") (pinfunction "1_1") (pintype "passive"))
    )
    (net (code "72") (name "Net-(U1-PB7(XTAL2{slash}TOSC2))") (class "Default")
      (node (ref "U1") (pin "8") (pinfunction "PB7(XTAL2/TOSC2)_8") (pintype "bidirectional"))
      (node (ref "Y1") (pin "3") (pinfunction "3_3") (pintype "passive"))
    )
    (net (code "73") (name "VCC") (class "Default")
      (node (ref "C9") (pin "+") (pinfunction "+_+") (pintype "passive"))
      (node (ref "D1") (pin "C") (pinfunction "C_C") (pintype "passive"))
      (node (ref "IC5") (pin "3") (pinfunction "VIN_3") (pintype "input"))
      (node (ref "JP3") (pin "1") (pinfunction "1_1") (pintype "passive"))
    )
    (net (code "74") (name "unconnected-(IC3-DOUT-Pad24)") (class "Default")
      (node (ref "IC3") (pin "24") (pinfunction "DOUT_24") (pintype "output"))
    )
    (net (code "75") (name "unconnected-(K1A-O-Pad3)") (class "Default")
      (node (ref "K1") (pin "3") (pinfunction "O_3") (pintype "passive"))
    )
    (net (code "76") (name "unconnected-(K1A-P-Pad4)") (class "Default")
      (node (ref "K1") (pin "4") (pinfunction "P_4") (pintype "passive"))
    )
    (net (code "77") (name "unconnected-(K1A-S-Pad5)") (class "Default")
      (node (ref "K1") (pin "5") (pinfunction "S_5") (pintype "passive"))
    )
    (net (code "78") (name "unconnected-(K1B-O-Pad10)") (class "Default")
      (node (ref "K1") (pin "10") (pinfunction "O_10") (pintype "passive"))
    )
    (net (code "79") (name "unconnected-(K1B-P-Pad9)") (class "Default")
      (node (ref "K1") (pin "9") (pinfunction "P_9") (pintype "passive"))
    )
    (net (code "80") (name "unconnected-(K1B-S-Pad8)") (class "Default")
      (node (ref "K1") (pin "8") (pinfunction "S_8") (pintype "passive"))
    )
    (net (code "81") (name "unconnected-(S1-S-Pad3)") (class "Default")
      (node (ref "S1") (pin "3") (pinfunction "S_3") (pintype "passive"))
    )
  )
)
